# T100CurrentMonitor.net
KiCad netlist of a schematic drawn in Altium Designer
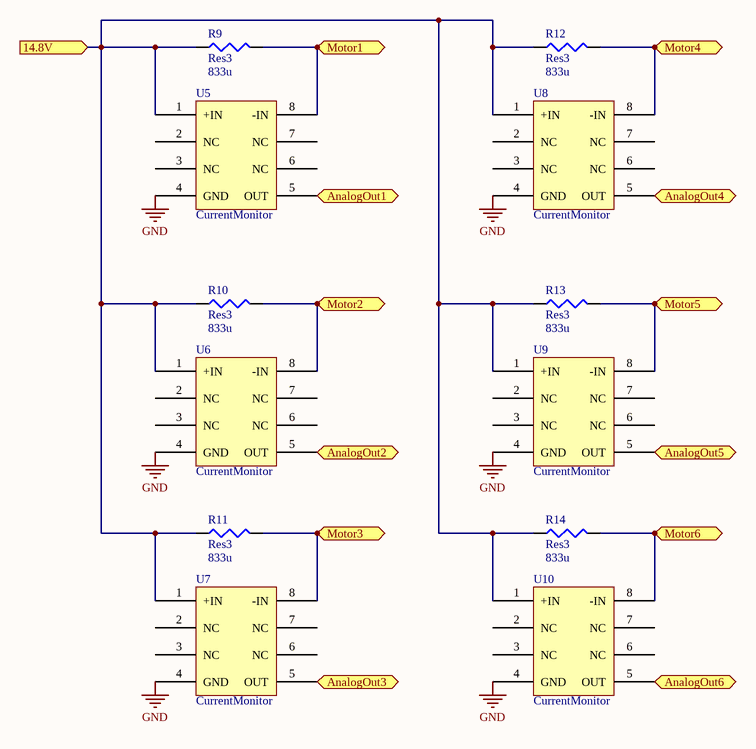
[diagram p0: T100CurrentMonitor.SchDoc]

(export (version "E")
  (design (tool "Eeschema 10.0.6"))
  (components
    (comp (ref "R9")
      (value "Res3")
      (footprint "Resistor075mohms")
      (description "Resistor")
      (fields (field (name "ALTIUM_VALUE") "833u") (field (name "PUBLISHER") "Altium Limited"))
      (libsource (lib "Miscellaneous Devices") (part "Res3"))
    )
    (comp (ref "R10")
      (value "Res3")
      (footprint "Resistor075mohms")
      (description "Resistor")
      (fields (field (name "ALTIUM_VALUE") "833u") (field (name "PUBLISHER") "Altium Limited"))
      (libsource (lib "Miscellaneous Devices") (part "Res3"))
    )
    (comp (ref "R11")
      (value "Res3")
      (footprint "Resistor075mohms")
      (description "Resistor")
      (fields (field (name "ALTIUM_VALUE") "833u") (field (name "PUBLISHER") "Altium Limited"))
      (libsource (lib "Miscellaneous Devices") (part "Res3"))
    )
    (comp (ref "R12")
      (value "Res3")
      (footprint "Resistor075mohms")
      (description "Resistor")
      (fields (field (name "ALTIUM_VALUE") "833u") (field (name "PUBLISHER") "Altium Limited"))
      (libsource (lib "Miscellaneous Devices") (part "Res3"))
    )
    (comp (ref "R13")
      (value "Res3")
      (footprint "Resistor075mohms")
      (description "Resistor")
      (fields (field (name "ALTIUM_VALUE") "833u") (field (name "PUBLISHER") "Altium Limited"))
      (libsource (lib "Miscellaneous Devices") (part "Res3"))
    )
    (comp (ref "R14")
      (value "Res3")
      (footprint "Resistor075mohms")
      (description "Resistor")
      (fields (field (name "ALTIUM_VALUE") "833u") (field (name "PUBLISHER") "Altium Limited"))
      (libsource (lib "Miscellaneous Devices") (part "Res3"))
    )
    (comp (ref "U5") (value "CurrentMonitor") (footprint "AD8217") (libsource (lib "AD8217") (part "AD8217")))
    (comp (ref "U6") (value "CurrentMonitor") (footprint "AD8217") (libsource (lib "AD8217") (part "AD8217")))
    (comp (ref "U7") (value "CurrentMonitor") (footprint "AD8217") (libsource (lib "AD8217") (part "AD8217")))
    (comp (ref "U8") (value "CurrentMonitor") (footprint "AD8217") (libsource (lib "AD8217") (part "AD8217")))
    (comp (ref "U9") (value "CurrentMonitor") (footprint "AD8217") (libsource (lib "AD8217") (part "AD8217")))
    (comp (ref "U10")
      (value "CurrentMonitor")
      (footprint "AD8217")
      (libsource (lib "AD8217") (part "AD8217"))
    )
  )
  (nets
    (net (code "1") (name "/14.8V") (class "Default")
      (node (ref "R10") (pin "1") (pinfunction "1_1") (pintype "passive"))
      (node (ref "R11") (pin "1") (pinfunction "1_1") (pintype "passive"))
      (node (ref "R12") (pin "1") (pinfunction "1_1") (pintype "passive"))
      (node (ref "R13") (pin "1") (pinfunction "1_1") (pintype "passive"))
      (node (ref "R14") (pin "1") (pinfunction "1_1") (pintype "passive"))
      (node (ref "R9") (pin "1") (pinfunction "1_1") (pintype "passive"))
      (node (ref "U10") (pin "1") (pinfunction "+IN_1") (pintype "passive"))
      (node (ref "U5") (pin "1") (pinfunction "+IN_1") (pintype "passive"))
      (node (ref "U6") (pin "1") (pinfunction "+IN_1") (pintype "passive"))
      (node (ref "U7") (pin "1") (pinfunction "+IN_1") (pintype "passive"))
      (node (ref "U8") (pin "1") (pinfunction "+IN_1") (pintype "passive"))
      (node (ref "U9") (pin "1") (pinfunction "+IN_1") (pintype "passive"))
    )
    (net (code "2") (name "/AnalogOut1") (class "Default")
      (node (ref "U5") (pin "5") (pinfunction "OUT_5") (pintype "passive"))
    )
    (net (code "3") (name "/AnalogOut2") (class "Default")
      (node (ref "U6") (pin "5") (pinfunction "OUT_5") (pintype "passive"))
    )
    (net (code "4") (name "/AnalogOut3") (class "Default")
      (node (ref "U7") (pin "5") (pinfunction "OUT_5") (pintype "passive"))
    )
    (net (code "5") (name "/AnalogOut4") (class "Default")
      (node (ref "U8") (pin "5") (pinfunction "OUT_5") (pintype "passive"))
    )
    (net (code "6") (name "/AnalogOut5") (class "Default")
      (node (ref "U9") (pin "5") (pinfunction "OUT_5") (pintype "passive"))
    )
    (net (code "7") (name "/AnalogOut6") (class "Default")
      (node (ref "U10") (pin "5") (pinfunction "OUT_5") (pintype "passive"))
    )
    (net (code "8") (name "/Motor1") (class "Default")
      (node (ref "R9") (pin "2") (pinfunction "2_2") (pintype "passive"))
      (node (ref "U5") (pin "8") (pinfunction "-IN_8") (pintype "passive"))
    )
    (net (code "9") (name "/Motor2") (class "Default")
      (node (ref "R10") (pin "2") (pinfunction "2_2") (pintype "passive"))
      (node (ref "U6") (pin "8") (pinfunction "-IN_8") (pintype "passive"))
    )
    (net (code "10") (name "/Motor3") (class "Default")
      (node (ref "R11") (pin "2") (pinfunction "2_2") (pintype "passive"))
      (node (ref "U7") (pin "8") (pinfunction "-IN_8") (pintype "passive"))
    )
    (net (code "11") (name "/Motor4") (class "Default")
      (node (ref "R12") (pin "2") (pinfunction "2_2") (pintype "passive"))
      (node (ref "U8") (pin "8") (pinfunction "-IN_8") (pintype "passive"))
    )
    (net (code "12") (name "/Motor5") (class "Default")
      (node (ref "R13") (pin "2") (pinfunction "2_2") (pintype "passive"))
      (node (ref "U9") (pin "8") (pinfunction "-IN_8") (pintype "passive"))
    )
    (net (code "13") (name "/Motor6") (class "Default")
      (node (ref "R14") (pin "2") (pinfunction "2_2") (pintype "passive"))
      (node (ref "U10") (pin "8") (pinfunction "-IN_8") (pintype "passive"))
    )
    (net (code "14") (name "GND") (class "Default")
      (node (ref "U10") (pin "4") (pinfunction "GND_4") (pintype "passive"))
      (node (ref "U5") (pin "4") (pinfunction "GND_4") (pintype "passive"))
      (node (ref "U6") (pin "4") (pinfunction "GND_4") (pintype "passive"))
      (node (ref "U7") (pin "4") (pinfunction "GND_4") (pintype "passive"))
      (node (ref "U8") (pin "4") (pinfunction "GND_4") (pintype "passive"))
      (node (ref "U9") (pin "4") (pinfunction "GND_4") (pintype "passive"))
    )
    (net (code "15") (name "unconnected-(U5-NC-Pad2)") (class "Default")
      (node (ref "U5") (pin "2") (pinfunction "NC_2") (pintype "passive"))
    )
    (net (code "16") (name "unconnected-(U5-NC-Pad3)") (class "Default")
      (node (ref "U5") (pin "3") (pinfunction "NC_3") (pintype "passive"))
    )
    (net (code "17") (name "unconnected-(U5-NC-Pad6)") (class "Default")
      (node (ref "U5") (pin "6") (pinfunction "NC_6") (pintype "passive"))
    )
    (net (code "18") (name "unconnected-(U5-NC-Pad7)") (class "Default")
      (node (ref "U5") (pin "7") (pinfunction "NC_7") (pintype "passive"))
    )
    (net (code "19") (name "unconnected-(U6-NC-Pad2)") (class "Default")
      (node (ref "U6") (pin "2") (pinfunction "NC_2") (pintype "passive"))
    )
    (net (code "20") (name "unconnected-(U6-NC-Pad3)") (class "Default")
      (node (ref "U6") (pin "3") (pinfunction "NC_3") (pintype "passive"))
    )
    (net (code "21") (name "unconnected-(U6-NC-Pad6)") (class "Default")
      (node (ref "U6") (pin "6") (pinfunction "NC_6") (pintype "passive"))
    )
    (net (code "22") (name "unconnected-(U6-NC-Pad7)") (class "Default")
      (node (ref "U6") (pin "7") (pinfunction "NC_7") (pintype "passive"))
    )
    (net (code "23") (name "unconnected-(U7-NC-Pad2)") (class "Default")
      (node (ref "U7") (pin "2") (pinfunction "NC_2") (pintype "passive"))
    )
    (net (code "24") (name "unconnected-(U7-NC-Pad3)") (class "Default")
      (node (ref "U7") (pin "3") (pinfunction "NC_3") (pintype "passive"))
    )
    (net (code "25") (name "unconnected-(U7-NC-Pad6)") (class "Default")
      (node (ref "U7") (pin "6") (pinfunction "NC_6") (pintype "passive"))
    )
    (net (code "26") (name "unconnected-(U7-NC-Pad7)") (class "Default")
      (node (ref "U7") (pin "7") (pinfunction "NC_7") (pintype "passive"))
    )
    (net (code "27") (name "unconnected-(U8-NC-Pad2)") (class "Default")
      (node (ref "U8") (pin "2") (pinfunction "NC_2") (pintype "passive"))
    )
    (net (code "28") (name "unconnected-(U8-NC-Pad3)") (class "Default")
      (node (ref "U8") (pin "3") (pinfunction "NC_3") (pintype "passive"))
    )
    (net (code "29") (name "unconnected-(U8-NC-Pad6)") (class "Default")
      (node (ref "U8") (pin "6") (pinfunction "NC_6") (pintype "passive"))
    )
    (net (code "30") (name "unconnected-(U8-NC-Pad7)") (class "Default")
      (node (ref "U8") (pin "7") (pinfunction "NC_7") (pintype "passive"))
    )
    (net (code "31") (name "unconnected-(U9-NC-Pad2)") (class "Default")
      (node (ref "U9") (pin "2") (pinfunction "NC_2") (pintype "passive"))
    )
    (net (code "32") (name "unconnected-(U9-NC-Pad3)") (class "Default")
      (node (ref "U9") (pin "3") (pinfunction "NC_3") (pintype "passive"))
    )
    (net (code "33") (name "unconnected-(U9-NC-Pad6)") (class "Default")
      (node (ref "U9") (pin "6") (pinfunction "NC_6") (pintype "passive"))
    )
    (net (code "34") (name "unconnected-(U9-NC-Pad7)") (class "Default")
      (node (ref "U9") (pin "7") (pinfunction "NC_7") (pintype "passive"))
    )
    (net (code "35") (name "unconnected-(U10-NC-Pad2)") (class "Default")
      (node (ref "U10") (pin "2") (pinfunction "NC_2") (pintype "passive"))
    )
    (net (code "36") (name "unconnected-(U10-NC-Pad3)") (class "Default")
      (node (ref "U10") (pin "3") (pinfunction "NC_3") (pintype "passive"))
    )
    (net (code "37") (name "unconnected-(U10-NC-Pad6)") (class "Default")
      (node (ref "U10") (pin "6") (pinfunction "NC_6") (pintype "passive"))
    )
    (net (code "38") (name "unconnected-(U10-NC-Pad7)") (class "Default")
      (node (ref "U10") (pin "7") (pinfunction "NC_7") (pintype "passive"))
    )
  )
)
